# t167.net
KiCad netlist of a schematic drawn in EAGLE
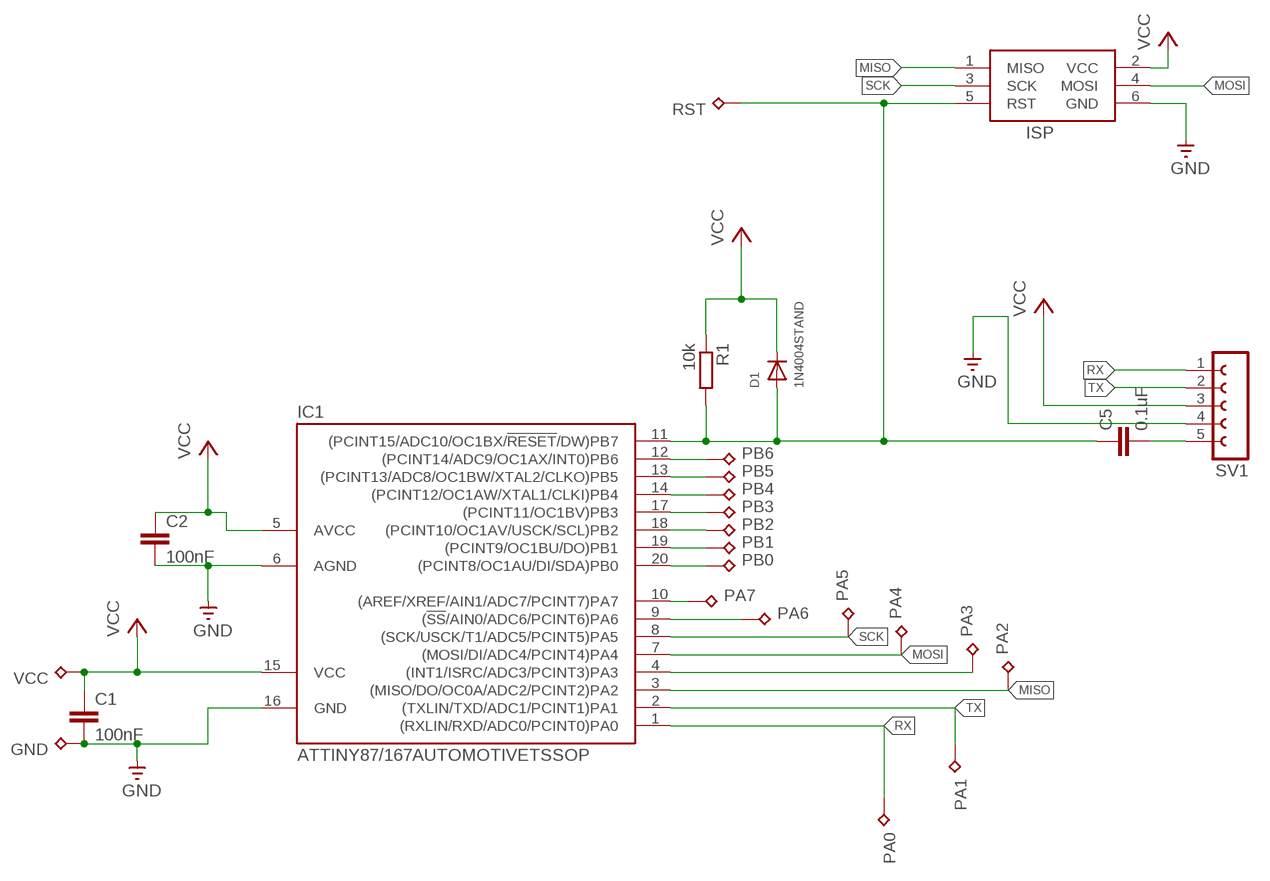
[diagram p0: schematic, sheet 1]

(export (version "E")
  (design (tool "Eeschema 10.0.6"))
  (components
    (comp (ref "C1")
      (value "100nF")
      (footprint "eagle-import:C0805")
      (libsource (lib "eagle-import") (part "C-EUC0805"))
    )
    (comp (ref "C2")
      (value "100nF")
      (footprint "eagle-import:C0805")
      (libsource (lib "eagle-import") (part "C-EUC0805"))
    )
    (comp (ref "C5")
      (value "0.1uF")
      (footprint "eagle-import:C0805K")
      (libsource (lib "eagle-import") (part "C-EUC0805K"))
    )
    (comp (ref "D1")
      (value "1N4004STAND")
      (footprint "eagle-import:SOD-323F")
      (libsource (lib "eagle-import") (part "DIODESOD-323F"))
    )
    (comp (ref "GND")
      (value "1XPIN-HEADER")
      (footprint "eagle-import:1XPIN-HEADER")
      (libsource (lib "eagle-import") (part "1XPIN-HEADER"))
    )
    (comp (ref "IC1")
      (value "ATTINY87/167AUTOMOTIVETSSOP")
      (footprint "eagle-import:TSSOP20")
      (libsource (lib "eagle-import") (part "ATTINY87/167AUTOMOTIVETSSOP"))
    )
    (comp (ref "ISP")
      (value "AVRISP-6")
      (footprint "eagle-import:AVRISP")
      (libsource (lib "eagle-import") (part "AVRISP-6"))
    )
    (comp (ref "PA0")
      (value "1XPIN-HEADER")
      (footprint "eagle-import:1XPIN-HEADER")
      (libsource (lib "eagle-import") (part "1XPIN-HEADER"))
    )
    (comp (ref "PA1")
      (value "1XPIN-HEADER")
      (footprint "eagle-import:1XPIN-HEADER")
      (libsource (lib "eagle-import") (part "1XPIN-HEADER"))
    )
    (comp (ref "PA2")
      (value "1XPIN-HEADER")
      (footprint "eagle-import:1XPIN-HEADER")
      (libsource (lib "eagle-import") (part "1XPIN-HEADER"))
    )
    (comp (ref "PA3")
      (value "1XPIN-HEADER")
      (footprint "eagle-import:1XPIN-HEADER")
      (libsource (lib "eagle-import") (part "1XPIN-HEADER"))
    )
    (comp (ref "PA4")
      (value "1XPIN-HEADER")
      (footprint "eagle-import:1XPIN-HEADER")
      (libsource (lib "eagle-import") (part "1XPIN-HEADER"))
    )
    (comp (ref "PA5")
      (value "1XPIN-HEADER")
      (footprint "eagle-import:1XPIN-HEADER")
      (libsource (lib "eagle-import") (part "1XPIN-HEADER"))
    )
    (comp (ref "PA6")
      (value "1XPIN-HEADER")
      (footprint "eagle-import:1XPIN-HEADER")
      (libsource (lib "eagle-import") (part "1XPIN-HEADER"))
    )
    (comp (ref "PA7")
      (value "1XPIN-HEADER")
      (footprint "eagle-import:1XPIN-HEADER")
      (libsource (lib "eagle-import") (part "1XPIN-HEADER"))
    )
    (comp (ref "PB0")
      (value "1XPIN-HEADER")
      (footprint "eagle-import:1XPIN-HEADER")
      (libsource (lib "eagle-import") (part "1XPIN-HEADER"))
    )
    (comp (ref "PB1")
      (value "1XPIN-HEADER")
      (footprint "eagle-import:1XPIN-HEADER")
      (libsource (lib "eagle-import") (part "1XPIN-HEADER"))
    )
    (comp (ref "PB2")
      (value "1XPIN-HEADER")
      (footprint "eagle-import:1XPIN-HEADER")
      (libsource (lib "eagle-import") (part "1XPIN-HEADER"))
    )
    (comp (ref "PB3")
      (value "1XPIN-HEADER")
      (footprint "eagle-import:1XPIN-HEADER")
      (libsource (lib "eagle-import") (part "1XPIN-HEADER"))
    )
    (comp (ref "PB4")
      (value "1XPIN-HEADER")
      (footprint "eagle-import:1XPIN-HEADER")
      (libsource (lib "eagle-import") (part "1XPIN-HEADER"))
    )
    (comp (ref "PB5")
      (value "1XPIN-HEADER")
      (footprint "eagle-import:1XPIN-HEADER")
      (libsource (lib "eagle-import") (part "1XPIN-HEADER"))
    )
    (comp (ref "PB6")
      (value "1XPIN-HEADER")
      (footprint "eagle-import:1XPIN-HEADER")
      (libsource (lib "eagle-import") (part "1XPIN-HEADER"))
    )
    (comp (ref "R1")
      (value "10k")
      (footprint "eagle-import:M0805")
      (libsource (lib "eagle-import") (part "R-EU_M0805"))
    )
    (comp (ref "RST")
      (value "1XPIN-HEADER")
      (footprint "eagle-import:1XPIN-HEADER")
      (libsource (lib "eagle-import") (part "1XPIN-HEADER"))
    )
    (comp (ref "SV1")
      (value "FE05-1")
      (footprint "eagle-import:FE05-1")
      (libsource (lib "eagle-import") (part "FE05-1"))
    )
    (comp (ref "VCC")
      (value "1XPIN-HEADER")
      (footprint "eagle-import:1XPIN-HEADER")
      (libsource (lib "eagle-import") (part "1XPIN-HEADER"))
    )
  )
  (nets
    (net (code "1") (name "GND") (class "Default")
      (node (ref "C1") (pin "2") (pinfunction "2_2") (pintype "passive"))
      (node (ref "C2") (pin "2") (pinfunction "2_2") (pintype "passive"))
      (node (ref "GND") (pin "P$1") (pinfunction "P$1_P$1") (pintype "bidirectional"))
      (node (ref "IC1") (pin "16") (pinfunction "GND_16") (pintype "power_in"))
      (node (ref "IC1") (pin "6") (pinfunction "AGND_6") (pintype "bidirectional"))
      (node (ref "ISP") (pin "6") (pinfunction "GND_6") (pintype "power_in"))
      (node (ref "SV1") (pin "4") (pinfunction "4_4") (pintype "passive"))
    )
    (net (code "2") (name "MISO") (class "Default")
      (node (ref "IC1") (pin "3") (pinfunction "(MISO/DO/OC0A/ADC2/PCINT2)PA2_3") (pintype "bidirectional"))
      (node (ref "ISP") (pin "1") (pinfunction "MISO_1") (pintype "input"))
      (node (ref "PA2") (pin "P$1") (pinfunction "P$1_P$1") (pintype "bidirectional"))
    )
    (net (code "3") (name "MOSI") (class "Default")
      (node (ref "IC1") (pin "7") (pinfunction "(MOSI/DI/ADC4/PCINT4)PA4_7") (pintype "bidirectional"))
      (node (ref "ISP") (pin "4") (pinfunction "MOSI_4") (pintype "output"))
      (node (ref "PA4") (pin "P$1") (pinfunction "P$1_P$1") (pintype "bidirectional"))
    )
    (net (code "4") (name "Net-(C5-Pad2)") (class "Default")
      (node (ref "C5") (pin "2") (pinfunction "2_2") (pintype "passive"))
      (node (ref "SV1") (pin "5") (pinfunction "5_5") (pintype "passive"))
    )
    (net (code "5") (name "Net-(IC1-(AREF{slash}XREF{slash}AIN1{slash}ADC7{slash}PCINT7)PA7)") (class "Default")
      (node (ref "IC1") (pin "10") (pinfunction "(AREF/XREF/AIN1/ADC7/PCINT7)PA7_10") (pintype "bidirectional"))
      (node (ref "PA7") (pin "P$1") (pinfunction "P$1_P$1") (pintype "bidirectional"))
    )
    (net (code "6") (name "Net-(IC1-(INT1{slash}ISRC{slash}ADC3{slash}PCINT3)PA3)") (class "Default")
      (node (ref "IC1") (pin "4") (pinfunction "(INT1/ISRC/ADC3/PCINT3)PA3_4") (pintype "bidirectional"))
      (node (ref "PA3") (pin "P$1") (pinfunction "P$1_P$1") (pintype "bidirectional"))
    )
    (net (code "7") (name "Net-(IC1-(PCINT8{slash}OC1AU{slash}DI{slash}SDA)PB0)") (class "Default")
      (node (ref "IC1") (pin "20") (pinfunction "(PCINT8/OC1AU/DI/SDA)PB0_20") (pintype "bidirectional"))
      (node (ref "PB0") (pin "P$1") (pinfunction "P$1_P$1") (pintype "bidirectional"))
    )
    (net (code "8") (name "Net-(IC1-(PCINT9{slash}OC1BU{slash}DO)PB1)") (class "Default")
      (node (ref "IC1") (pin "19") (pinfunction "(PCINT9/OC1BU/DO)PB1_19") (pintype "bidirectional"))
      (node (ref "PB1") (pin "P$1") (pinfunction "P$1_P$1") (pintype "bidirectional"))
    )
    (net (code "9") (name "Net-(IC1-(PCINT10{slash}OC1AV{slash}USCK{slash}SCL)PB2)") (class "Default")
      (node (ref "IC1") (pin "18") (pinfunction "(PCINT10/OC1AV/USCK/SCL)PB2_18") (pintype "bidirectional"))
      (node (ref "PB2") (pin "P$1") (pinfunction "P$1_P$1") (pintype "bidirectional"))
    )
    (net (code "10") (name "Net-(IC1-(PCINT11{slash}OC1BV)PB3)") (class "Default")
      (node (ref "IC1") (pin "17") (pinfunction "(PCINT11/OC1BV)PB3_17") (pintype "bidirectional"))
      (node (ref "PB3") (pin "P$1") (pinfunction "P$1_P$1") (pintype "bidirectional"))
    )
    (net (code "11") (name "Net-(IC1-(PCINT12{slash}OC1AW{slash}XTAL1{slash}CLKI)PB4)") (class "Default")
      (node (ref "IC1") (pin "14") (pinfunction "(PCINT12/OC1AW/XTAL1/CLKI)PB4_14") (pintype "bidirectional"))
      (node (ref "PB4") (pin "P$1") (pinfunction "P$1_P$1") (pintype "bidirectional"))
    )
    (net (code "12") (name "Net-(IC1-(PCINT13{slash}ADC8{slash}OC1BW{slash}XTAL2{slash}CLKO)PB5)") (class "Default")
      (node (ref "IC1") (pin "13") (pinfunction "(PCINT13/ADC8/OC1BW/XTAL2/CLKO)PB5_13") (pintype "bidirectional"))
      (node (ref "PB5") (pin "P$1") (pinfunction "P$1_P$1") (pintype "bidirectional"))
    )
    (net (code "13") (name "Net-(IC1-(PCINT14{slash}ADC9{slash}OC1AX{slash}INT0)PB6)") (class "Default")
      (node (ref "IC1") (pin "12") (pinfunction "(PCINT14/ADC9/OC1AX/INT0)PB6_12") (pintype "bidirectional"))
      (node (ref "PB6") (pin "P$1") (pinfunction "P$1_P$1") (pintype "bidirectional"))
    )
    (net (code "14") (name "Net-(IC1-(PCINT15{slash}ADC10{slash}OC1BX{slash}~{RESET}{slash}DW)PB7)") (class "Default")
      (node (ref "C5") (pin "1") (pinfunction "1_1") (pintype "passive"))
      (node (ref "D1") (pin "A") (pinfunction "A_A") (pintype "passive"))
      (node (ref "IC1") (pin "11") (pinfunction "(PCINT15/ADC10/OC1BX/~{RESET}/DW)PB7_11") (pintype "bidirectional"))
      (node (ref "ISP") (pin "5") (pinfunction "RST_5") (pintype "output"))
      (node (ref "R1") (pin "2") (pinfunction "2_2") (pintype "passive"))
      (node (ref "RST") (pin "P$1") (pinfunction "P$1_P$1") (pintype "bidirectional"))
    )
    (net (code "15") (name "Net-(IC1-(~{SS}{slash}AIN0{slash}ADC6{slash}PCINT6)PA6)") (class "Default")
      (node (ref "IC1") (pin "9") (pinfunction "(~{SS}/AIN0/ADC6/PCINT6)PA6_9") (pintype "bidirectional"))
      (node (ref "PA6") (pin "P$1") (pinfunction "P$1_P$1") (pintype "bidirectional"))
    )
    (net (code "16") (name "RX") (class "Default")
      (node (ref "IC1") (pin "1") (pinfunction "(RXLIN/RXD/ADC0/PCINT0)PA0_1") (pintype "bidirectional"))
      (node (ref "PA0") (pin "P$1") (pinfunction "P$1_P$1") (pintype "bidirectional"))
      (node (ref "SV1") (pin "1") (pinfunction "1_1") (pintype "passive"))
    )
    (net (code "17") (name "SCK") (class "Default")
      (node (ref "IC1") (pin "8") (pinfunction "(SCK/USCK/T1/ADC5/PCINT5)PA5_8") (pintype "bidirectional"))
      (node (ref "ISP") (pin "3") (pinfunction "SCK_3") (pintype "output"))
      (node (ref "PA5") (pin "P$1") (pinfunction "P$1_P$1") (pintype "bidirectional"))
    )
    (net (code "18") (name "TX") (class "Default")
      (node (ref "IC1") (pin "2") (pinfunction "(TXLIN/TXD/ADC1/PCINT1)PA1_2") (pintype "bidirectional"))
      (node (ref "PA1") (pin "P$1") (pinfunction "P$1_P$1") (pintype "bidirectional"))
      (node (ref "SV1") (pin "2") (pinfunction "2_2") (pintype "passive"))
    )
    (net (code "19") (name "VCC") (class "Default")
      (node (ref "C1") (pin "1") (pinfunction "1_1") (pintype "passive"))
      (node (ref "C2") (pin "1") (pinfunction "1_1") (pintype "passive"))
      (node (ref "D1") (pin "C") (pinfunction "C_C") (pintype "passive"))
      (node (ref "IC1") (pin "15") (pinfunction "VCC_15") (pintype "power_in"))
      (node (ref "IC1") (pin "5") (pinfunction "AVCC_5") (pintype "bidirectional"))
      (node (ref "ISP") (pin "2") (pinfunction "VCC_2") (pintype "power_in"))
      (node (ref "R1") (pin "1") (pinfunction "1_1") (pintype "passive"))
      (node (ref "SV1") (pin "3") (pinfunction "3_3") (pintype "passive"))
      (node (ref "VCC") (pin "P$1") (pinfunction "P$1_P$1") (pintype "bidirectional"))
    )
  )
)
